# target.net
KiCad netlist of a schematic drawn in EAGLE
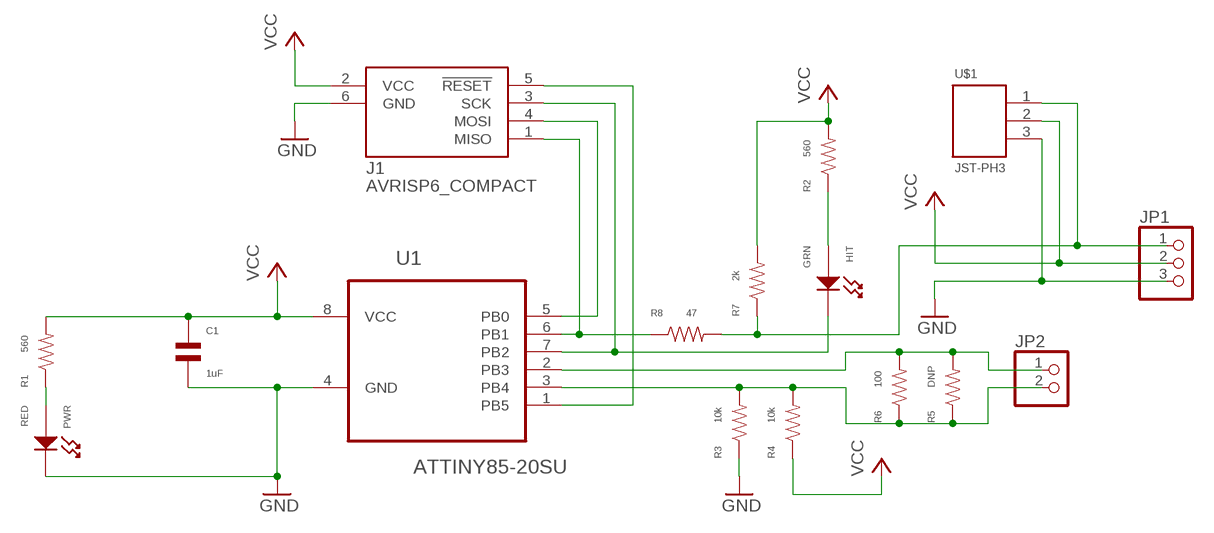
[diagram p0: schematic, sheet 1]

(export (version "E")
  (design (tool "Eeschema 10.0.6"))
  (components
    (comp (ref "C1")
      (value "1uF")
      (footprint "eagle-import:C0603")
      (libsource (lib "eagle-import") (part "CAPACITOR_NP_0603"))
    )
    (comp (ref "HIT")
      (value "GRN")
      (footprint "eagle-import:LED0603")
      (libsource (lib "eagle-import") (part "LED_SINGLE_0603"))
    )
    (comp (ref "J1")
      (value "AVRISP6_COMPACT")
      (footprint "eagle-import:CON6P2R")
      (libsource (lib "eagle-import") (part "AVRISP6_COMPACT"))
    )
    (comp (ref "JP1")
      (value "PINHD-1X3")
      (footprint "eagle-import:1X03")
      (libsource (lib "eagle-import") (part "PINHD-1X3"))
    )
    (comp (ref "JP2")
      (value "PINHD-1X2")
      (footprint "eagle-import:1X02")
      (libsource (lib "eagle-import") (part "PINHD-1X2"))
    )
    (comp (ref "PWR")
      (value "RED")
      (footprint "eagle-import:LED0603")
      (libsource (lib "eagle-import") (part "LED_SINGLE_0603"))
    )
    (comp (ref "R1")
      (value "560")
      (footprint "eagle-import:R0603")
      (libsource (lib "eagle-import") (part "RESISTOR_0603"))
    )
    (comp (ref "R2")
      (value "560")
      (footprint "eagle-import:R0603")
      (libsource (lib "eagle-import") (part "RESISTOR_0603"))
    )
    (comp (ref "R3")
      (value "10k")
      (footprint "eagle-import:R0603")
      (libsource (lib "eagle-import") (part "RESISTOR_0603"))
    )
    (comp (ref "R4")
      (value "10k")
      (footprint "eagle-import:R0603")
      (libsource (lib "eagle-import") (part "RESISTOR_0603"))
    )
    (comp (ref "R5")
      (value "DNP")
      (footprint "eagle-import:R0603")
      (libsource (lib "eagle-import") (part "RESISTOR_0603"))
    )
    (comp (ref "R6")
      (value "100")
      (footprint "eagle-import:R0603")
      (libsource (lib "eagle-import") (part "RESISTOR_0603"))
    )
    (comp (ref "R7")
      (value "2k")
      (footprint "eagle-import:R0603")
      (libsource (lib "eagle-import") (part "RESISTOR_0603"))
    )
    (comp (ref "R8")
      (value "47")
      (footprint "eagle-import:R0603")
      (libsource (lib "eagle-import") (part "RESISTOR_0603"))
    )
    (comp (ref "U$1")
      (value "JST-PH3")
      (footprint "eagle-import:JST-PH3")
      (libsource (lib "eagle-import") (part "JST-PH3"))
    )
    (comp (ref "U1")
      (value "ATTINY85-20SU")
      (footprint "eagle-import:SOIC127P798X216-8N")
      (libsource (lib "eagle-import") (part "ATTINY85-20SU"))
    )
  )
  (nets
    (net (code "1") (name "GND") (class "Default")
      (node (ref "C1") (pin "P$2") (pinfunction "P$2_P$2") (pintype "passive"))
      (node (ref "J1") (pin "6") (pinfunction "GND_6") (pintype "power_in"))
      (node (ref "JP1") (pin "3") (pinfunction "3_3") (pintype "passive"))
      (node (ref "PWR") (pin "CATHODE") (pinfunction "CATHODE_CATHODE") (pintype "power_in"))
      (node (ref "R3") (pin "P$1") (pinfunction "P$1_P$1") (pintype "passive"))
      (node (ref "U$1") (pin "3") (pinfunction "3_3") (pintype "passive"))
      (node (ref "U1") (pin "4") (pinfunction "GND_4") (pintype "passive"))
    )
    (net (code "2") (name "Net-(HIT-PadANODE)") (class "Default")
      (node (ref "HIT") (pin "ANODE") (pinfunction "ANODE_ANODE") (pintype "power_in"))
      (node (ref "R2") (pin "P$1") (pinfunction "P$1_P$1") (pintype "passive"))
    )
    (net (code "3") (name "Net-(J1-MISO)") (class "Default")
      (node (ref "J1") (pin "1") (pinfunction "MISO_1") (pintype "input"))
      (node (ref "R8") (pin "P$1") (pinfunction "P$1_P$1") (pintype "passive"))
      (node (ref "U1") (pin "6") (pinfunction "PB1_6") (pintype "bidirectional"))
    )
    (net (code "4") (name "Net-(J1-MOSI)") (class "Default")
      (node (ref "J1") (pin "4") (pinfunction "MOSI_4") (pintype "output"))
      (node (ref "U1") (pin "5") (pinfunction "PB0_5") (pintype "bidirectional"))
    )
    (net (code "5") (name "Net-(J1-SCK)") (class "Default")
      (node (ref "HIT") (pin "CATHODE") (pinfunction "CATHODE_CATHODE") (pintype "power_in"))
      (node (ref "J1") (pin "3") (pinfunction "SCK_3") (pintype "output"))
      (node (ref "U1") (pin "7") (pinfunction "PB2_7") (pintype "bidirectional"))
    )
    (net (code "6") (name "Net-(J1-~{RESET})") (class "Default")
      (node (ref "J1") (pin "5") (pinfunction "~{RESET}_5") (pintype "output"))
      (node (ref "U1") (pin "1") (pinfunction "PB5_1") (pintype "bidirectional"))
    )
    (net (code "7") (name "Net-(JP1-Pad1)") (class "Default")
      (node (ref "JP1") (pin "1") (pinfunction "1_1") (pintype "passive"))
      (node (ref "R7") (pin "P$1") (pinfunction "P$1_P$1") (pintype "passive"))
      (node (ref "R8") (pin "P$2") (pinfunction "P$2_P$2") (pintype "passive"))
      (node (ref "U$1") (pin "1") (pinfunction "1_1") (pintype "passive"))
    )
    (net (code "8") (name "Net-(PWR-PadANODE)") (class "Default")
      (node (ref "PWR") (pin "ANODE") (pinfunction "ANODE_ANODE") (pintype "power_in"))
      (node (ref "R1") (pin "P$1") (pinfunction "P$1_P$1") (pintype "passive"))
    )
    (net (code "9") (name "Net-(U1-PB3)") (class "Default")
      (node (ref "JP2") (pin "1") (pinfunction "1_1") (pintype "passive"))
      (node (ref "R5") (pin "P$2") (pinfunction "P$2_P$2") (pintype "passive"))
      (node (ref "R6") (pin "P$2") (pinfunction "P$2_P$2") (pintype "passive"))
      (node (ref "U1") (pin "2") (pinfunction "PB3_2") (pintype "bidirectional"))
    )
    (net (code "10") (name "Net-(U1-PB4)") (class "Default")
      (node (ref "JP2") (pin "2") (pinfunction "2_2") (pintype "passive"))
      (node (ref "R3") (pin "P$2") (pinfunction "P$2_P$2") (pintype "passive"))
      (node (ref "R4") (pin "P$2") (pinfunction "P$2_P$2") (pintype "passive"))
      (node (ref "R5") (pin "P$1") (pinfunction "P$1_P$1") (pintype "passive"))
      (node (ref "R6") (pin "P$1") (pinfunction "P$1_P$1") (pintype "passive"))
      (node (ref "U1") (pin "3") (pinfunction "PB4_3") (pintype "bidirectional"))
    )
    (net (code "11") (name "VCC") (class "Default")
      (node (ref "C1") (pin "P$1") (pinfunction "P$1_P$1") (pintype "passive"))
      (node (ref "J1") (pin "2") (pinfunction "VCC_2") (pintype "power_in"))
      (node (ref "JP1") (pin "2") (pinfunction "2_2") (pintype "passive"))
      (node (ref "R1") (pin "P$2") (pinfunction "P$2_P$2") (pintype "passive"))
      (node (ref "R2") (pin "P$2") (pinfunction "P$2_P$2") (pintype "passive"))
      (node (ref "R4") (pin "P$1") (pinfunction "P$1_P$1") (pintype "passive"))
      (node (ref "R7") (pin "P$2") (pinfunction "P$2_P$2") (pintype "passive"))
      (node (ref "U$1") (pin "2") (pinfunction "2_2") (pintype "passive"))
      (node (ref "U1") (pin "8") (pinfunction "VCC_8") (pintype "power_in"))
    )
  )
)
